# R113B.net
KiCad netlist of a schematic drawn in EAGLE
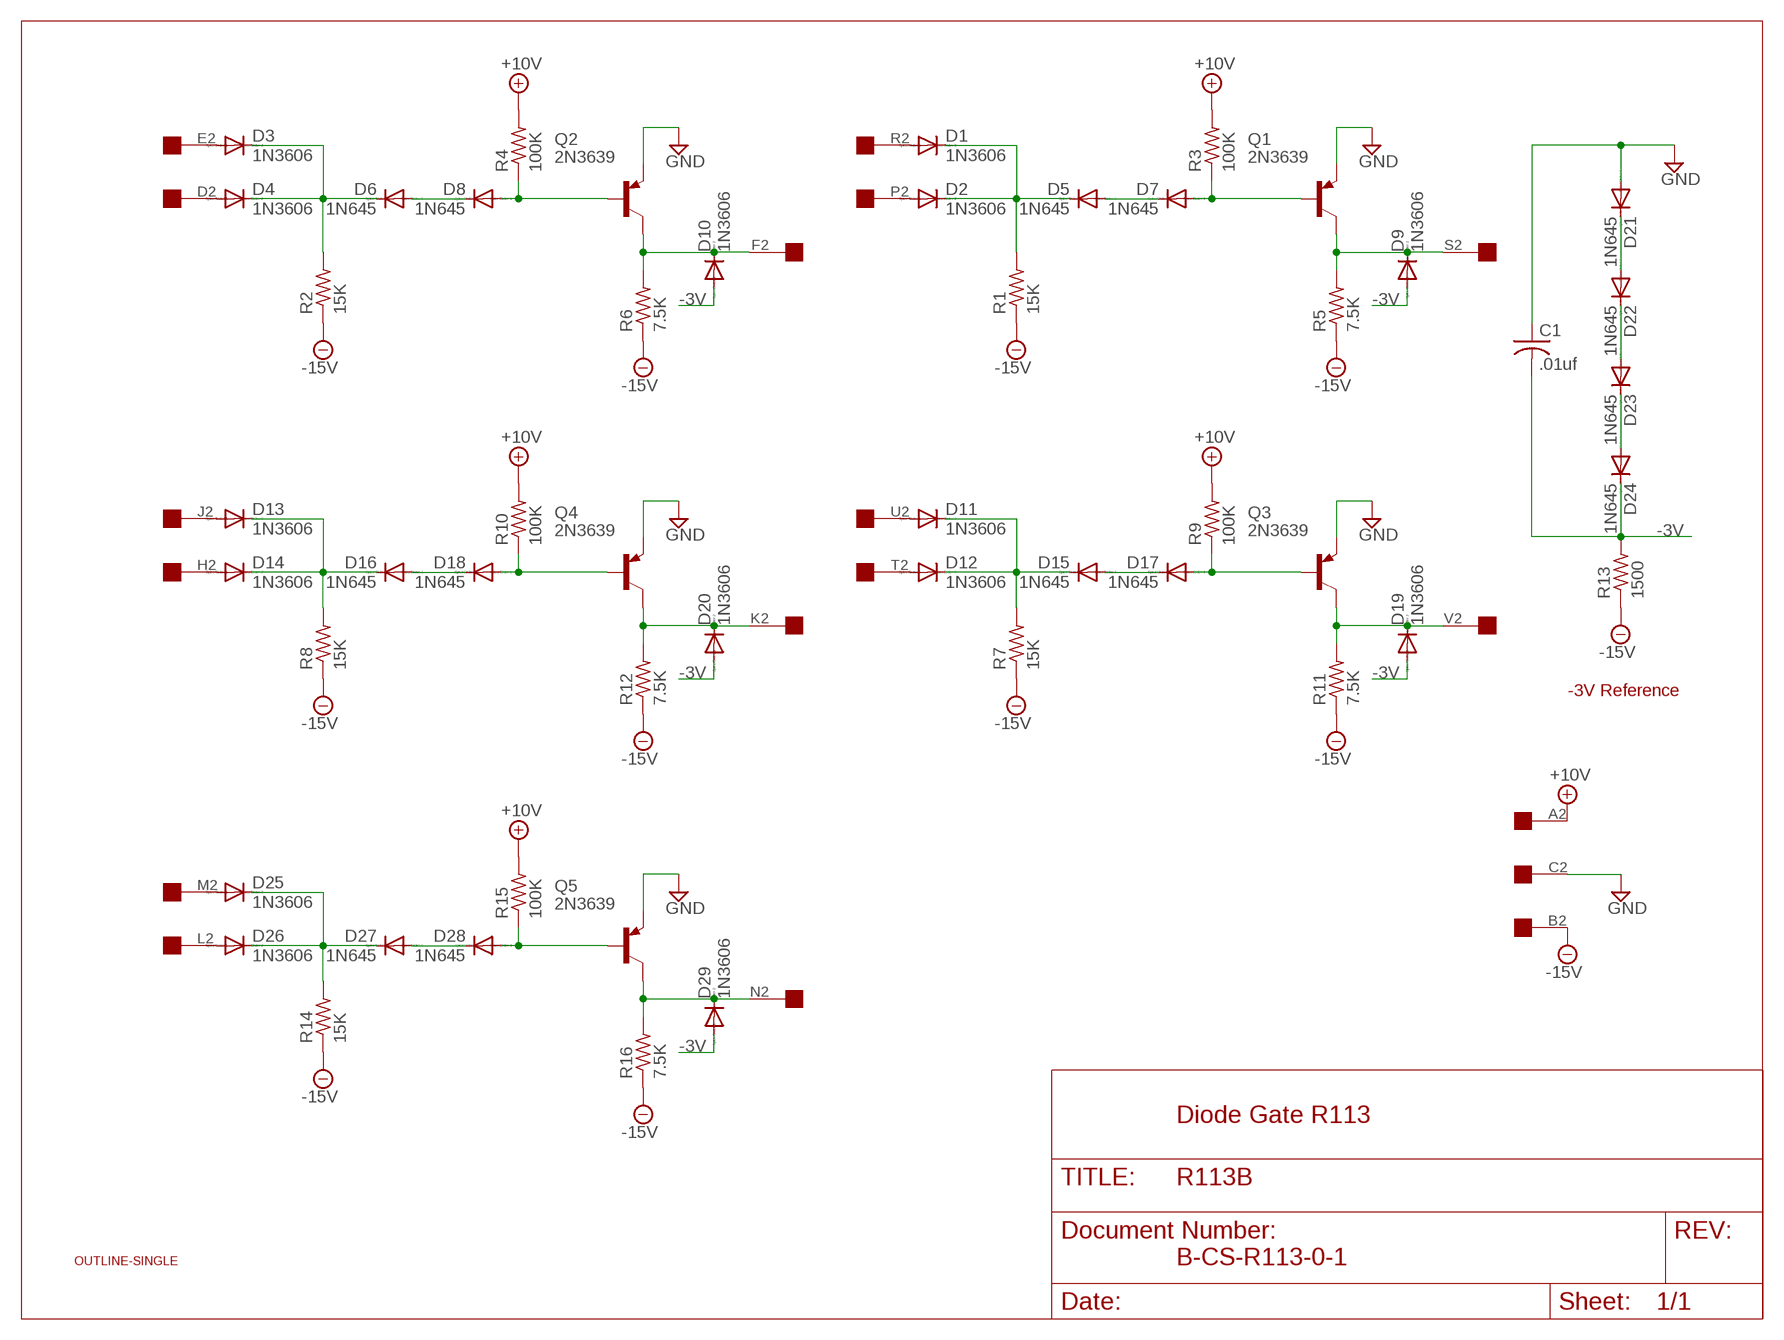
[diagram p0: schematic, sheet 1]

(export (version "E")
  (design (tool "Eeschema 10.0.6"))
  (components
    (comp (ref "C1")
      (value ".01uf")
      (footprint "eagle-import:C050-025X075")
      (libsource (lib "eagle-import") (part "C-US050-025X075"))
    )
    (comp (ref "D1")
      (value "1N3606")
      (footprint "eagle-import:DO35-10")
      (libsource (lib "eagle-import") (part "1N4148DO35-10"))
    )
    (comp (ref "D2")
      (value "1N3606")
      (footprint "eagle-import:DO35-10")
      (libsource (lib "eagle-import") (part "1N4148DO35-10"))
    )
    (comp (ref "D3")
      (value "1N3606")
      (footprint "eagle-import:DO35-10")
      (libsource (lib "eagle-import") (part "1N4148DO35-10"))
    )
    (comp (ref "D4")
      (value "1N3606")
      (footprint "eagle-import:DO35-10")
      (libsource (lib "eagle-import") (part "1N4148DO35-10"))
    )
    (comp (ref "D5")
      (value "1N645")
      (footprint "eagle-import:DO35-10")
      (libsource (lib "eagle-import") (part "1N4148DO35-10"))
    )
    (comp (ref "D6")
      (value "1N645")
      (footprint "eagle-import:DO35-10")
      (libsource (lib "eagle-import") (part "1N4148DO35-10"))
    )
    (comp (ref "D7")
      (value "1N645")
      (footprint "eagle-import:DO35-10")
      (libsource (lib "eagle-import") (part "1N4148DO35-10"))
    )
    (comp (ref "D8")
      (value "1N645")
      (footprint "eagle-import:DO35-10")
      (libsource (lib "eagle-import") (part "1N4148DO35-10"))
    )
    (comp (ref "D9")
      (value "1N3606")
      (footprint "eagle-import:DO35-10")
      (libsource (lib "eagle-import") (part "1N4148DO35-10"))
    )
    (comp (ref "D10")
      (value "1N3606")
      (footprint "eagle-import:DO35-10")
      (libsource (lib "eagle-import") (part "1N4148DO35-10"))
    )
    (comp (ref "D11")
      (value "1N3606")
      (footprint "eagle-import:DO35-10")
      (libsource (lib "eagle-import") (part "1N4148DO35-10"))
    )
    (comp (ref "D12")
      (value "1N3606")
      (footprint "eagle-import:DO35-10")
      (libsource (lib "eagle-import") (part "1N4148DO35-10"))
    )
    (comp (ref "D13")
      (value "1N3606")
      (footprint "eagle-import:DO35-10")
      (libsource (lib "eagle-import") (part "1N4148DO35-10"))
    )
    (comp (ref "D14")
      (value "1N3606")
      (footprint "eagle-import:DO35-10")
      (libsource (lib "eagle-import") (part "1N4148DO35-10"))
    )
    (comp (ref "D15")
      (value "1N645")
      (footprint "eagle-import:DO35-10")
      (libsource (lib "eagle-import") (part "1N4148DO35-10"))
    )
    (comp (ref "D16")
      (value "1N645")
      (footprint "eagle-import:DO35-10")
      (libsource (lib "eagle-import") (part "1N4148DO35-10"))
    )
    (comp (ref "D17")
      (value "1N645")
      (footprint "eagle-import:DO35-10")
      (libsource (lib "eagle-import") (part "1N4148DO35-10"))
    )
    (comp (ref "D18")
      (value "1N645")
      (footprint "eagle-import:DO35-10")
      (libsource (lib "eagle-import") (part "1N4148DO35-10"))
    )
    (comp (ref "D19")
      (value "1N3606")
      (footprint "eagle-import:DO35-10")
      (libsource (lib "eagle-import") (part "1N4148DO35-10"))
    )
    (comp (ref "D20")
      (value "1N3606")
      (footprint "eagle-import:DO35-10")
      (libsource (lib "eagle-import") (part "1N4148DO35-10"))
    )
    (comp (ref "D21")
      (value "1N645")
      (footprint "eagle-import:DO35-10")
      (libsource (lib "eagle-import") (part "1N4148DO35-10"))
    )
    (comp (ref "D22")
      (value "1N645")
      (footprint "eagle-import:DO35-10")
      (libsource (lib "eagle-import") (part "1N4148DO35-10"))
    )
    (comp (ref "D23")
      (value "1N645")
      (footprint "eagle-import:DO35-10")
      (libsource (lib "eagle-import") (part "1N4148DO35-10"))
    )
    (comp (ref "D24")
      (value "1N645")
      (footprint "eagle-import:DO35-10")
      (libsource (lib "eagle-import") (part "1N4148DO35-10"))
    )
    (comp (ref "D25")
      (value "1N3606")
      (footprint "eagle-import:DO35-10")
      (libsource (lib "eagle-import") (part "1N4148DO35-10"))
    )
    (comp (ref "D26")
      (value "1N3606")
      (footprint "eagle-import:DO35-10")
      (libsource (lib "eagle-import") (part "1N4148DO35-10"))
    )
    (comp (ref "D27")
      (value "1N645")
      (footprint "eagle-import:DO35-10")
      (libsource (lib "eagle-import") (part "1N4148DO35-10"))
    )
    (comp (ref "D28")
      (value "1N645")
      (footprint "eagle-import:DO35-10")
      (libsource (lib "eagle-import") (part "1N4148DO35-10"))
    )
    (comp (ref "D29")
      (value "1N3606")
      (footprint "eagle-import:DO35-10")
      (libsource (lib "eagle-import") (part "1N4148DO35-10"))
    )
    (comp (ref "Q1")
      (value "2N3639")
      (footprint "eagle-import:TO39")
      (libsource (lib "eagle-import") (part "2N3637"))
    )
    (comp (ref "Q2")
      (value "2N3639")
      (footprint "eagle-import:TO39")
      (libsource (lib "eagle-import") (part "2N3637"))
    )
    (comp (ref "Q3")
      (value "2N3639")
      (footprint "eagle-import:TO39")
      (libsource (lib "eagle-import") (part "2N3637"))
    )
    (comp (ref "Q4")
      (value "2N3639")
      (footprint "eagle-import:TO39")
      (libsource (lib "eagle-import") (part "2N3637"))
    )
    (comp (ref "Q5")
      (value "2N3639")
      (footprint "eagle-import:TO39")
      (libsource (lib "eagle-import") (part "2N3637"))
    )
    (comp (ref "R1")
      (value "15K")
      (footprint "eagle-import:0207_10")
      (libsource (lib "eagle-import") (part "R-US_0207/10"))
    )
    (comp (ref "R2")
      (value "15K")
      (footprint "eagle-import:0207_10")
      (libsource (lib "eagle-import") (part "R-US_0207/10"))
    )
    (comp (ref "R3")
      (value "100K")
      (footprint "eagle-import:0207_10")
      (libsource (lib "eagle-import") (part "R-US_0207/10"))
    )
    (comp (ref "R4")
      (value "100K")
      (footprint "eagle-import:0207_10")
      (libsource (lib "eagle-import") (part "R-US_0207/10"))
    )
    (comp (ref "R5")
      (value "7.5K")
      (footprint "eagle-import:0207_10")
      (libsource (lib "eagle-import") (part "R-US_0207/10"))
    )
    (comp (ref "R6")
      (value "7.5K")
      (footprint "eagle-import:0207_10")
      (libsource (lib "eagle-import") (part "R-US_0207/10"))
    )
    (comp (ref "R7")
      (value "15K")
      (footprint "eagle-import:0207_10")
      (libsource (lib "eagle-import") (part "R-US_0207/10"))
    )
    (comp (ref "R8")
      (value "15K")
      (footprint "eagle-import:0207_10")
      (libsource (lib "eagle-import") (part "R-US_0207/10"))
    )
    (comp (ref "R9")
      (value "100K")
      (footprint "eagle-import:0207_10")
      (libsource (lib "eagle-import") (part "R-US_0207/10"))
    )
    (comp (ref "R10")
      (value "100K")
      (footprint "eagle-import:0207_10")
      (libsource (lib "eagle-import") (part "R-US_0207/10"))
    )
    (comp (ref "R11")
      (value "7.5K")
      (footprint "eagle-import:0207_10")
      (libsource (lib "eagle-import") (part "R-US_0207/10"))
    )
    (comp (ref "R12")
      (value "7.5K")
      (footprint "eagle-import:0207_10")
      (libsource (lib "eagle-import") (part "R-US_0207/10"))
    )
    (comp (ref "R13")
      (value "1500")
      (footprint "eagle-import:0207_10")
      (libsource (lib "eagle-import") (part "R-US_0207/10"))
    )
    (comp (ref "R14")
      (value "15K")
      (footprint "eagle-import:0207_10")
      (libsource (lib "eagle-import") (part "R-US_0207/10"))
    )
    (comp (ref "R15")
      (value "100K")
      (footprint "eagle-import:0207_10")
      (libsource (lib "eagle-import") (part "R-US_0207/10"))
    )
    (comp (ref "R16")
      (value "7.5K")
      (footprint "eagle-import:0207_10")
      (libsource (lib "eagle-import") (part "R-US_0207/10"))
    )
    (comp (ref "U$1")
      (value "OUTLINE-SINGLE")
      (footprint "eagle-import:SINGLE")
      (libsource (lib "eagle-import") (part "OUTLINE-SINGLE"))
    )
    (comp (ref "U$2")
      (value "EDGE-1")
      (footprint "eagle-import:EDGE-CON1")
      (libsource (lib "eagle-import") (part "EDGE-1"))
    )
  )
  (nets
    (net (code "1") (name "+10V") (class "Default")
      (node (ref "R10") (pin "2") (pinfunction "2_2") (pintype "passive"))
      (node (ref "R15") (pin "2") (pinfunction "2_2") (pintype "passive"))
      (node (ref "R3") (pin "2") (pinfunction "2_2") (pintype "passive"))
      (node (ref "R4") (pin "2") (pinfunction "2_2") (pintype "passive"))
      (node (ref "R9") (pin "2") (pinfunction "2_2") (pintype "passive"))
      (node (ref "U$2") (pin "A2") (pinfunction "1_A2") (pintype "bidirectional"))
    )
    (net (code "2") (name "-15V") (class "Default")
      (node (ref "R1") (pin "1") (pinfunction "1_1") (pintype "passive"))
      (node (ref "R11") (pin "1") (pinfunction "1_1") (pintype "passive"))
      (node (ref "R12") (pin "1") (pinfunction "1_1") (pintype "passive"))
      (node (ref "R13") (pin "1") (pinfunction "1_1") (pintype "passive"))
      (node (ref "R14") (pin "1") (pinfunction "1_1") (pintype "passive"))
      (node (ref "R16") (pin "1") (pinfunction "1_1") (pintype "passive"))
      (node (ref "R2") (pin "1") (pinfunction "1_1") (pintype "passive"))
      (node (ref "R5") (pin "1") (pinfunction "1_1") (pintype "passive"))
      (node (ref "R6") (pin "1") (pinfunction "1_1") (pintype "passive"))
      (node (ref "R7") (pin "1") (pinfunction "1_1") (pintype "passive"))
      (node (ref "R8") (pin "1") (pinfunction "1_1") (pintype "passive"))
      (node (ref "U$2") (pin "B2") (pinfunction "1_B2") (pintype "bidirectional"))
    )
    (net (code "3") (name "/-3V") (class "Default")
      (node (ref "C1") (pin "2") (pinfunction "2_2") (pintype "passive"))
      (node (ref "D10") (pin "A") (pinfunction "A_A") (pintype "passive"))
      (node (ref "D19") (pin "A") (pinfunction "A_A") (pintype "passive"))
      (node (ref "D20") (pin "A") (pinfunction "A_A") (pintype "passive"))
      (node (ref "D24") (pin "C") (pinfunction "C_C") (pintype "passive"))
      (node (ref "D29") (pin "A") (pinfunction "A_A") (pintype "passive"))
      (node (ref "D9") (pin "A") (pinfunction "A_A") (pintype "passive"))
      (node (ref "R13") (pin "2") (pinfunction "2_2") (pintype "passive"))
    )
    (net (code "4") (name "GND") (class "Default")
      (node (ref "C1") (pin "1") (pinfunction "1_1") (pintype "passive"))
      (node (ref "D21") (pin "A") (pinfunction "A_A") (pintype "passive"))
      (node (ref "Q1") (pin "1") (pinfunction "E_1") (pintype "passive"))
      (node (ref "Q2") (pin "1") (pinfunction "E_1") (pintype "passive"))
      (node (ref "Q3") (pin "1") (pinfunction "E_1") (pintype "passive"))
      (node (ref "Q4") (pin "1") (pinfunction "E_1") (pintype "passive"))
      (node (ref "Q5") (pin "1") (pinfunction "E_1") (pintype "passive"))
      (node (ref "U$2") (pin "C2") (pinfunction "1_C2") (pintype "bidirectional"))
    )
    (net (code "5") (name "Net-(D1-PadC)") (class "Default")
      (node (ref "D1") (pin "C") (pinfunction "C_C") (pintype "passive"))
      (node (ref "D2") (pin "C") (pinfunction "C_C") (pintype "passive"))
      (node (ref "D5") (pin "C") (pinfunction "C_C") (pintype "passive"))
      (node (ref "R1") (pin "2") (pinfunction "2_2") (pintype "passive"))
    )
    (net (code "6") (name "Net-(D3-PadC)") (class "Default")
      (node (ref "D3") (pin "C") (pinfunction "C_C") (pintype "passive"))
      (node (ref "D4") (pin "C") (pinfunction "C_C") (pintype "passive"))
      (node (ref "D6") (pin "C") (pinfunction "C_C") (pintype "passive"))
      (node (ref "R2") (pin "2") (pinfunction "2_2") (pintype "passive"))
    )
    (net (code "7") (name "Net-(D5-PadA)") (class "Default")
      (node (ref "D5") (pin "A") (pinfunction "A_A") (pintype "passive"))
      (node (ref "D7") (pin "C") (pinfunction "C_C") (pintype "passive"))
    )
    (net (code "8") (name "Net-(D6-PadA)") (class "Default")
      (node (ref "D6") (pin "A") (pinfunction "A_A") (pintype "passive"))
      (node (ref "D8") (pin "C") (pinfunction "C_C") (pintype "passive"))
    )
    (net (code "9") (name "Net-(D11-PadC)") (class "Default")
      (node (ref "D11") (pin "C") (pinfunction "C_C") (pintype "passive"))
      (node (ref "D12") (pin "C") (pinfunction "C_C") (pintype "passive"))
      (node (ref "D15") (pin "C") (pinfunction "C_C") (pintype "passive"))
      (node (ref "R7") (pin "2") (pinfunction "2_2") (pintype "passive"))
    )
    (net (code "10") (name "Net-(D13-PadC)") (class "Default")
      (node (ref "D13") (pin "C") (pinfunction "C_C") (pintype "passive"))
      (node (ref "D14") (pin "C") (pinfunction "C_C") (pintype "passive"))
      (node (ref "D16") (pin "C") (pinfunction "C_C") (pintype "passive"))
      (node (ref "R8") (pin "2") (pinfunction "2_2") (pintype "passive"))
    )
    (net (code "11") (name "Net-(D15-PadA)") (class "Default")
      (node (ref "D15") (pin "A") (pinfunction "A_A") (pintype "passive"))
      (node (ref "D17") (pin "C") (pinfunction "C_C") (pintype "passive"))
    )
    (net (code "12") (name "Net-(D16-PadA)") (class "Default")
      (node (ref "D16") (pin "A") (pinfunction "A_A") (pintype "passive"))
      (node (ref "D18") (pin "C") (pinfunction "C_C") (pintype "passive"))
    )
    (net (code "13") (name "Net-(D21-PadC)") (class "Default")
      (node (ref "D21") (pin "C") (pinfunction "C_C") (pintype "passive"))
      (node (ref "D22") (pin "A") (pinfunction "A_A") (pintype "passive"))
    )
    (net (code "14") (name "Net-(D22-PadC)") (class "Default")
      (node (ref "D22") (pin "C") (pinfunction "C_C") (pintype "passive"))
      (node (ref "D23") (pin "A") (pinfunction "A_A") (pintype "passive"))
    )
    (net (code "15") (name "Net-(D23-PadC)") (class "Default")
      (node (ref "D23") (pin "C") (pinfunction "C_C") (pintype "passive"))
      (node (ref "D24") (pin "A") (pinfunction "A_A") (pintype "passive"))
    )
    (net (code "16") (name "Net-(D25-PadC)") (class "Default")
      (node (ref "D25") (pin "C") (pinfunction "C_C") (pintype "passive"))
      (node (ref "D26") (pin "C") (pinfunction "C_C") (pintype "passive"))
      (node (ref "D27") (pin "C") (pinfunction "C_C") (pintype "passive"))
      (node (ref "R14") (pin "2") (pinfunction "2_2") (pintype "passive"))
    )
    (net (code "17") (name "Net-(D27-PadA)") (class "Default")
      (node (ref "D27") (pin "A") (pinfunction "A_A") (pintype "passive"))
      (node (ref "D28") (pin "C") (pinfunction "C_C") (pintype "passive"))
    )
    (net (code "18") (name "Net-(Q1-B)") (class "Default")
      (node (ref "D7") (pin "A") (pinfunction "A_A") (pintype "passive"))
      (node (ref "Q1") (pin "2") (pinfunction "B_2") (pintype "passive"))
      (node (ref "R3") (pin "1") (pinfunction "1_1") (pintype "passive"))
    )
    (net (code "19") (name "Net-(Q1-C)") (class "Default")
      (node (ref "D9") (pin "C") (pinfunction "C_C") (pintype "passive"))
      (node (ref "Q1") (pin "3") (pinfunction "C_3") (pintype "passive"))
      (node (ref "R5") (pin "2") (pinfunction "2_2") (pintype "passive"))
      (node (ref "U$2") (pin "S2") (pinfunction "1_S2") (pintype "bidirectional"))
    )
    (net (code "20") (name "Net-(Q2-B)") (class "Default")
      (node (ref "D8") (pin "A") (pinfunction "A_A") (pintype "passive"))
      (node (ref "Q2") (pin "2") (pinfunction "B_2") (pintype "passive"))
      (node (ref "R4") (pin "1") (pinfunction "1_1") (pintype "passive"))
    )
    (net (code "21") (name "Net-(Q2-C)") (class "Default")
      (node (ref "D10") (pin "C") (pinfunction "C_C") (pintype "passive"))
      (node (ref "Q2") (pin "3") (pinfunction "C_3") (pintype "passive"))
      (node (ref "R6") (pin "2") (pinfunction "2_2") (pintype "passive"))
      (node (ref "U$2") (pin "F2") (pinfunction "1_F2") (pintype "bidirectional"))
    )
    (net (code "22") (name "Net-(Q3-B)") (class "Default")
      (node (ref "D17") (pin "A") (pinfunction "A_A") (pintype "passive"))
      (node (ref "Q3") (pin "2") (pinfunction "B_2") (pintype "passive"))
      (node (ref "R9") (pin "1") (pinfunction "1_1") (pintype "passive"))
    )
    (net (code "23") (name "Net-(Q3-C)") (class "Default")
      (node (ref "D19") (pin "C") (pinfunction "C_C") (pintype "passive"))
      (node (ref "Q3") (pin "3") (pinfunction "C_3") (pintype "passive"))
      (node (ref "R11") (pin "2") (pinfunction "2_2") (pintype "passive"))
      (node (ref "U$2") (pin "V2") (pinfunction "1_V2") (pintype "bidirectional"))
    )
    (net (code "24") (name "Net-(Q4-B)") (class "Default")
      (node (ref "D18") (pin "A") (pinfunction "A_A") (pintype "passive"))
      (node (ref "Q4") (pin "2") (pinfunction "B_2") (pintype "passive"))
      (node (ref "R10") (pin "1") (pinfunction "1_1") (pintype "passive"))
    )
    (net (code "25") (name "Net-(Q4-C)") (class "Default")
      (node (ref "D20") (pin "C") (pinfunction "C_C") (pintype "passive"))
      (node (ref "Q4") (pin "3") (pinfunction "C_3") (pintype "passive"))
      (node (ref "R12") (pin "2") (pinfunction "2_2") (pintype "passive"))
      (node (ref "U$2") (pin "K2") (pinfunction "1_K2") (pintype "bidirectional"))
    )
    (net (code "26") (name "Net-(Q5-B)") (class "Default")
      (node (ref "D28") (pin "A") (pinfunction "A_A") (pintype "passive"))
      (node (ref "Q5") (pin "2") (pinfunction "B_2") (pintype "passive"))
      (node (ref "R15") (pin "1") (pinfunction "1_1") (pintype "passive"))
    )
    (net (code "27") (name "Net-(Q5-C)") (class "Default")
      (node (ref "D29") (pin "C") (pinfunction "C_C") (pintype "passive"))
      (node (ref "Q5") (pin "3") (pinfunction "C_3") (pintype "passive"))
      (node (ref "R16") (pin "2") (pinfunction "2_2") (pintype "passive"))
      (node (ref "U$2") (pin "N2") (pinfunction "1_N2") (pintype "bidirectional"))
    )
    (net (code "28") (name "Net-(U$2D-1)") (class "Default")
      (node (ref "D4") (pin "A") (pinfunction "A_A") (pintype "passive"))
      (node (ref "U$2") (pin "D2") (pinfunction "1_D2") (pintype "bidirectional"))
    )
    (net (code "29") (name "Net-(U$2E-1)") (class "Default")
      (node (ref "D3") (pin "A") (pinfunction "A_A") (pintype "passive"))
      (node (ref "U$2") (pin "E2") (pinfunction "1_E2") (pintype "bidirectional"))
    )
    (net (code "30") (name "Net-(U$2G-1)") (class "Default")
      (node (ref "D14") (pin "A") (pinfunction "A_A") (pintype "passive"))
      (node (ref "U$2") (pin "H2") (pinfunction "1_H2") (pintype "bidirectional"))
    )
    (net (code "31") (name "Net-(U$2H-1)") (class "Default")
      (node (ref "D13") (pin "A") (pinfunction "A_A") (pintype "passive"))
      (node (ref "U$2") (pin "J2") (pinfunction "1_J2") (pintype "bidirectional"))
    )
    (net (code "32") (name "Net-(U$2J-1)") (class "Default")
      (node (ref "D26") (pin "A") (pinfunction "A_A") (pintype "passive"))
      (node (ref "U$2") (pin "L2") (pinfunction "1_L2") (pintype "bidirectional"))
    )
    (net (code "33") (name "Net-(U$2K-1)") (class "Default")
      (node (ref "D25") (pin "A") (pinfunction "A_A") (pintype "passive"))
      (node (ref "U$2") (pin "M2") (pinfunction "1_M2") (pintype "bidirectional"))
    )
    (net (code "34") (name "Net-(U$2M-1)") (class "Default")
      (node (ref "D2") (pin "A") (pinfunction "A_A") (pintype "passive"))
      (node (ref "U$2") (pin "P2") (pinfunction "1_P2") (pintype "bidirectional"))
    )
    (net (code "35") (name "Net-(U$2N-1)") (class "Default")
      (node (ref "D1") (pin "A") (pinfunction "A_A") (pintype "passive"))
      (node (ref "U$2") (pin "R2") (pinfunction "1_R2") (pintype "bidirectional"))
    )
    (net (code "36") (name "Net-(U$2P-1)") (class "Default")
      (node (ref "D12") (pin "A") (pinfunction "A_A") (pintype "passive"))
      (node (ref "U$2") (pin "T2") (pinfunction "1_T2") (pintype "bidirectional"))
    )
    (net (code "37") (name "Net-(U$2Q-1)") (class "Default")
      (node (ref "D11") (pin "A") (pinfunction "A_A") (pintype "passive"))
      (node (ref "U$2") (pin "U2") (pinfunction "1_U2") (pintype "bidirectional"))
    )
  )
)
